# basic_schematic_io.net
KiCad netlist of a schematic drawn in EAGLE
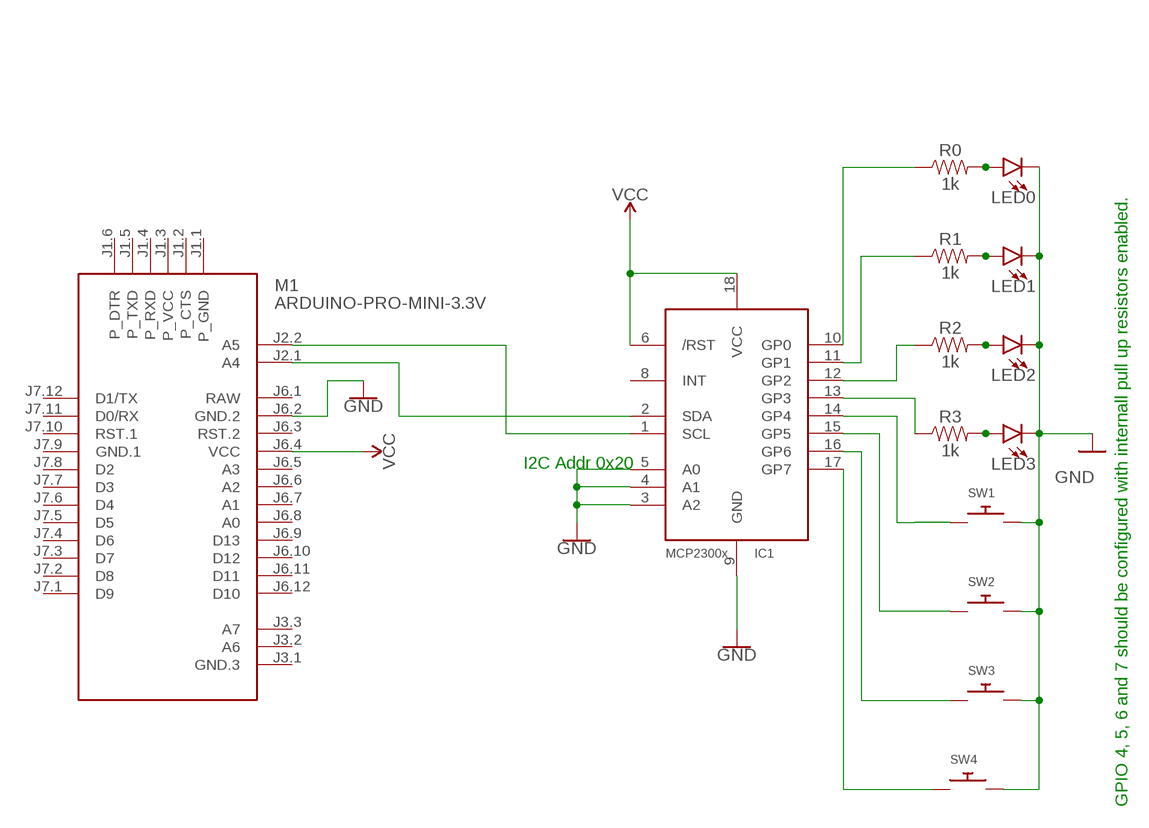
[diagram p0: schematic, sheet 1]

(export (version "E")
  (design (tool "Eeschema 10.0.6"))
  (components
    (comp (ref "IC1")
      (value "MCP23008/SO")
      (footprint "eagle-import:SO18W")
      (libsource (lib "eagle-import") (part "MCP23008/SO"))
    )
    (comp (ref "LED0")
      (value "LED3MM")
      (footprint "eagle-import:LED_3MM")
      (libsource (lib "eagle-import") (part "LED3MM"))
    )
    (comp (ref "LED1")
      (value "LED3MM")
      (footprint "eagle-import:LED_3MM")
      (libsource (lib "eagle-import") (part "LED3MM"))
    )
    (comp (ref "LED2")
      (value "LED3MM")
      (footprint "eagle-import:LED_3MM")
      (libsource (lib "eagle-import") (part "LED3MM"))
    )
    (comp (ref "LED3")
      (value "LED3MM")
      (footprint "eagle-import:LED_3MM")
      (libsource (lib "eagle-import") (part "LED3MM"))
    )
    (comp (ref "M1")
      (value "ARDUINO-PRO-MINI-3.3V")
      (footprint "eagle-import:ARDUINO-PRO-MINI")
      (libsource (lib "eagle-import") (part "ARDUINO-PRO-MINI-3.3V"))
    )
    (comp (ref "R0")
      (value "1k")
      (footprint "eagle-import:0603")
      (libsource (lib "eagle-import") (part "1KOHM-0603-1/10W-1%"))
    )
    (comp (ref "R1")
      (value "1k")
      (footprint "eagle-import:0603")
      (libsource (lib "eagle-import") (part "1KOHM-0603-1/10W-1%"))
    )
    (comp (ref "R2")
      (value "1k")
      (footprint "eagle-import:0603")
      (libsource (lib "eagle-import") (part "1KOHM-0603-1/10W-1%"))
    )
    (comp (ref "R3")
      (value "1k")
      (footprint "eagle-import:0603")
      (libsource (lib "eagle-import") (part "1KOHM-0603-1/10W-1%"))
    )
    (comp (ref "SW1")
      (value "SWITCH_PUSHBUTTONC&K_KSS")
      (footprint "eagle-import:BTN_CK_KSS")
      (libsource (lib "eagle-import") (part "SWITCH_PUSHBUTTONC&K_KSS"))
    )
    (comp (ref "SW2")
      (value "SWITCH_PUSHBUTTONC&K_KSS")
      (footprint "eagle-import:BTN_CK_KSS")
      (libsource (lib "eagle-import") (part "SWITCH_PUSHBUTTONC&K_KSS"))
    )
    (comp (ref "SW3")
      (value "SWITCH_PUSHBUTTONC&K_KSS")
      (footprint "eagle-import:BTN_CK_KSS")
      (libsource (lib "eagle-import") (part "SWITCH_PUSHBUTTONC&K_KSS"))
    )
    (comp (ref "SW4")
      (value "SWITCH_PUSHBUTTONC&K_KSS")
      (footprint "eagle-import:BTN_CK_KSS")
      (libsource (lib "eagle-import") (part "SWITCH_PUSHBUTTONC&K_KSS"))
    )
  )
  (nets
    (net (code "1") (name "/GND.1") (class "Default")
      (node (ref "M1") (pin "J7.9") (pinfunction "GND.1_J7.9") (pintype "power_in"))
    )
    (net (code "2") (name "/RAW") (class "Default")
      (node (ref "M1") (pin "J6.1") (pinfunction "RAW_J6.1") (pintype "power_in"))
    )
    (net (code "3") (name "GND") (class "Default")
      (node (ref "IC1") (pin "3") (pinfunction "A2_3") (pintype "input"))
      (node (ref "IC1") (pin "4") (pinfunction "A1_4") (pintype "input"))
      (node (ref "IC1") (pin "5") (pinfunction "A0_5") (pintype "input"))
      (node (ref "IC1") (pin "9") (pinfunction "GND_9") (pintype "power_in"))
      (node (ref "LED0") (pin "K") (pinfunction "C_K") (pintype "passive"))
      (node (ref "LED1") (pin "K") (pinfunction "C_K") (pintype "passive"))
      (node (ref "LED2") (pin "K") (pinfunction "C_K") (pintype "passive"))
      (node (ref "LED3") (pin "K") (pinfunction "C_K") (pintype "passive"))
      (node (ref "M1") (pin "J6.2") (pinfunction "GND.2_J6.2") (pintype "power_in"))
      (node (ref "SW1") (pin "P$2") (pinfunction "P$2_P$2") (pintype "passive"))
      (node (ref "SW2") (pin "P$2") (pinfunction "P$2_P$2") (pintype "passive"))
      (node (ref "SW3") (pin "P$2") (pinfunction "P$2_P$2") (pintype "passive"))
      (node (ref "SW4") (pin "P$2") (pinfunction "P$2_P$2") (pintype "passive"))
    )
    (net (code "4") (name "Net-(IC1-GP0)") (class "Default")
      (node (ref "IC1") (pin "10") (pinfunction "GP0_10") (pintype "bidirectional"))
      (node (ref "R0") (pin "1") (pinfunction "1_1") (pintype "passive"))
    )
    (net (code "5") (name "Net-(IC1-GP1)") (class "Default")
      (node (ref "IC1") (pin "11") (pinfunction "GP1_11") (pintype "bidirectional"))
      (node (ref "R1") (pin "1") (pinfunction "1_1") (pintype "passive"))
    )
    (net (code "6") (name "Net-(IC1-GP2)") (class "Default")
      (node (ref "IC1") (pin "12") (pinfunction "GP2_12") (pintype "bidirectional"))
      (node (ref "R2") (pin "1") (pinfunction "1_1") (pintype "passive"))
    )
    (net (code "7") (name "Net-(IC1-GP3)") (class "Default")
      (node (ref "IC1") (pin "13") (pinfunction "GP3_13") (pintype "bidirectional"))
      (node (ref "R3") (pin "1") (pinfunction "1_1") (pintype "passive"))
    )
    (net (code "8") (name "Net-(IC1-GP4)") (class "Default")
      (node (ref "IC1") (pin "14") (pinfunction "GP4_14") (pintype "bidirectional"))
      (node (ref "SW1") (pin "P$1") (pinfunction "P$1_P$1") (pintype "passive"))
    )
    (net (code "9") (name "Net-(IC1-GP5)") (class "Default")
      (node (ref "IC1") (pin "15") (pinfunction "GP5_15") (pintype "bidirectional"))
      (node (ref "SW2") (pin "P$1") (pinfunction "P$1_P$1") (pintype "passive"))
    )
    (net (code "10") (name "Net-(IC1-GP6)") (class "Default")
      (node (ref "IC1") (pin "16") (pinfunction "GP6_16") (pintype "bidirectional"))
      (node (ref "SW3") (pin "P$1") (pinfunction "P$1_P$1") (pintype "passive"))
    )
    (net (code "11") (name "Net-(IC1-GP7)") (class "Default")
      (node (ref "IC1") (pin "17") (pinfunction "GP7_17") (pintype "bidirectional"))
      (node (ref "SW4") (pin "P$1") (pinfunction "P$1_P$1") (pintype "passive"))
    )
    (net (code "12") (name "Net-(IC1-SCL)") (class "Default")
      (node (ref "IC1") (pin "1") (pinfunction "SCL_1") (pintype "bidirectional"))
      (node (ref "M1") (pin "J2.2") (pinfunction "A5_J2.2") (pintype "bidirectional"))
    )
    (net (code "13") (name "Net-(IC1-SDA)") (class "Default")
      (node (ref "IC1") (pin "2") (pinfunction "SDA_2") (pintype "bidirectional"))
      (node (ref "M1") (pin "J2.1") (pinfunction "A4_J2.1") (pintype "bidirectional"))
    )
    (net (code "14") (name "Net-(LED0-PadA)") (class "Default")
      (node (ref "LED0") (pin "A") (pinfunction "A_A") (pintype "passive"))
      (node (ref "R0") (pin "2") (pinfunction "2_2") (pintype "passive"))
    )
    (net (code "15") (name "Net-(LED1-PadA)") (class "Default")
      (node (ref "LED1") (pin "A") (pinfunction "A_A") (pintype "passive"))
      (node (ref "R1") (pin "2") (pinfunction "2_2") (pintype "passive"))
    )
    (net (code "16") (name "Net-(LED2-PadA)") (class "Default")
      (node (ref "LED2") (pin "A") (pinfunction "A_A") (pintype "passive"))
      (node (ref "R2") (pin "2") (pinfunction "2_2") (pintype "passive"))
    )
    (net (code "17") (name "Net-(LED3-PadA)") (class "Default")
      (node (ref "LED3") (pin "A") (pinfunction "A_A") (pintype "passive"))
      (node (ref "R3") (pin "2") (pinfunction "2_2") (pintype "passive"))
    )
    (net (code "18") (name "VCC") (class "Default")
      (node (ref "IC1") (pin "18") (pinfunction "VCC_18") (pintype "power_in"))
      (node (ref "IC1") (pin "6") (pinfunction "/RST_6") (pintype "input"))
      (node (ref "M1") (pin "J6.4") (pinfunction "VCC_J6.4") (pintype "power_in"))
    )
    (net (code "19") (name "unconnected-(IC1-INT-Pad8)") (class "Default")
      (node (ref "IC1") (pin "8") (pinfunction "INT_8") (pintype "output"))
    )
    (net (code "20") (name "unconnected-(M1-A0-PadJ6.8)") (class "Default")
      (node (ref "M1") (pin "J6.8") (pinfunction "A0_J6.8") (pintype "bidirectional"))
    )
    (net (code "21") (name "unconnected-(M1-A1-PadJ6.7)") (class "Default")
      (node (ref "M1") (pin "J6.7") (pinfunction "A1_J6.7") (pintype "bidirectional"))
    )
    (net (code "22") (name "unconnected-(M1-A2-PadJ6.6)") (class "Default")
      (node (ref "M1") (pin "J6.6") (pinfunction "A2_J6.6") (pintype "bidirectional"))
    )
    (net (code "23") (name "unconnected-(M1-A3-PadJ6.5)") (class "Default")
      (node (ref "M1") (pin "J6.5") (pinfunction "A3_J6.5") (pintype "bidirectional"))
    )
    (net (code "24") (name "unconnected-(M1-A6-PadJ3.2)") (class "Default")
      (node (ref "M1") (pin "J3.2") (pinfunction "A6_J3.2") (pintype "bidirectional"))
    )
    (net (code "25") (name "unconnected-(M1-A7-PadJ3.3)") (class "Default")
      (node (ref "M1") (pin "J3.3") (pinfunction "A7_J3.3") (pintype "bidirectional"))
    )
    (net (code "26") (name "unconnected-(M1-D0{slash}RX-PadJ7.11)") (class "Default")
      (node (ref "M1") (pin "J7.11") (pinfunction "D0/RX_J7.11") (pintype "bidirectional"))
    )
    (net (code "27") (name "unconnected-(M1-D1{slash}TX-PadJ7.12)") (class "Default")
      (node (ref "M1") (pin "J7.12") (pinfunction "D1/TX_J7.12") (pintype "bidirectional"))
    )
    (net (code "28") (name "unconnected-(M1-D2-PadJ7.8)") (class "Default")
      (node (ref "M1") (pin "J7.8") (pinfunction "D2_J7.8") (pintype "bidirectional"))
    )
    (net (code "29") (name "unconnected-(M1-D3-PadJ7.7)") (class "Default")
      (node (ref "M1") (pin "J7.7") (pinfunction "D3_J7.7") (pintype "bidirectional"))
    )
    (net (code "30") (name "unconnected-(M1-D4-PadJ7.6)") (class "Default")
      (node (ref "M1") (pin "J7.6") (pinfunction "D4_J7.6") (pintype "bidirectional"))
    )
    (net (code "31") (name "unconnected-(M1-D5-PadJ7.5)") (class "Default")
      (node (ref "M1") (pin "J7.5") (pinfunction "D5_J7.5") (pintype "bidirectional"))
    )
    (net (code "32") (name "unconnected-(M1-D6-PadJ7.4)") (class "Default")
      (node (ref "M1") (pin "J7.4") (pinfunction "D6_J7.4") (pintype "bidirectional"))
    )
    (net (code "33") (name "unconnected-(M1-D7-PadJ7.3)") (class "Default")
      (node (ref "M1") (pin "J7.3") (pinfunction "D7_J7.3") (pintype "bidirectional"))
    )
    (net (code "34") (name "unconnected-(M1-D8-PadJ7.2)") (class "Default")
      (node (ref "M1") (pin "J7.2") (pinfunction "D8_J7.2") (pintype "bidirectional"))
    )
    (net (code "35") (name "unconnected-(M1-D9-PadJ7.1)") (class "Default")
      (node (ref "M1") (pin "J7.1") (pinfunction "D9_J7.1") (pintype "bidirectional"))
    )
    (net (code "36") (name "unconnected-(M1-D10-PadJ6.12)") (class "Default")
      (node (ref "M1") (pin "J6.12") (pinfunction "D10_J6.12") (pintype "bidirectional"))
    )
    (net (code "37") (name "unconnected-(M1-D11-PadJ6.11)") (class "Default")
      (node (ref "M1") (pin "J6.11") (pinfunction "D11_J6.11") (pintype "bidirectional"))
    )
    (net (code "38") (name "unconnected-(M1-D12-PadJ6.10)") (class "Default")
      (node (ref "M1") (pin "J6.10") (pinfunction "D12_J6.10") (pintype "bidirectional"))
    )
    (net (code "39") (name "unconnected-(M1-D13-PadJ6.9)") (class "Default")
      (node (ref "M1") (pin "J6.9") (pinfunction "D13_J6.9") (pintype "bidirectional"))
    )
    (net (code "40") (name "unconnected-(M1-GND.3-PadJ3.1)") (class "Default")
      (node (ref "M1") (pin "J3.1") (pinfunction "GND.3_J3.1") (pintype "bidirectional"))
    )
    (net (code "41") (name "unconnected-(M1-P_CTS-PadJ1.2)") (class "Default")
      (node (ref "M1") (pin "J1.2") (pinfunction "P_CTS_J1.2") (pintype "bidirectional"))
    )
    (net (code "42") (name "unconnected-(M1-P_DTR-PadJ1.6)") (class "Default")
      (node (ref "M1") (pin "J1.6") (pinfunction "P_DTR_J1.6") (pintype "bidirectional"))
    )
    (net (code "43") (name "unconnected-(M1-P_GND-PadJ1.1)") (class "Default")
      (node (ref "M1") (pin "J1.1") (pinfunction "P_GND_J1.1") (pintype "bidirectional"))
    )
    (net (code "44") (name "unconnected-(M1-P_RXD-PadJ1.4)") (class "Default")
      (node (ref "M1") (pin "J1.4") (pinfunction "P_RXD_J1.4") (pintype "bidirectional"))
    )
    (net (code "45") (name "unconnected-(M1-P_TXD-PadJ1.5)") (class "Default")
      (node (ref "M1") (pin "J1.5") (pinfunction "P_TXD_J1.5") (pintype "bidirectional"))
    )
    (net (code "46") (name "unconnected-(M1-P_VCC-PadJ1.3)") (class "Default")
      (node (ref "M1") (pin "J1.3") (pinfunction "P_VCC_J1.3") (pintype "bidirectional"))
    )
    (net (code "47") (name "unconnected-(M1-RST.1-PadJ7.10)") (class "Default")
      (node (ref "M1") (pin "J7.10") (pinfunction "RST.1_J7.10") (pintype "bidirectional"))
    )
    (net (code "48") (name "unconnected-(M1-RST.2-PadJ6.3)") (class "Default")
      (node (ref "M1") (pin "J6.3") (pinfunction "RST.2_J6.3") (pintype "bidirectional"))
    )
  )
)
